# XMICRO-7SEG.net
KiCad netlist of a schematic drawn in EAGLE
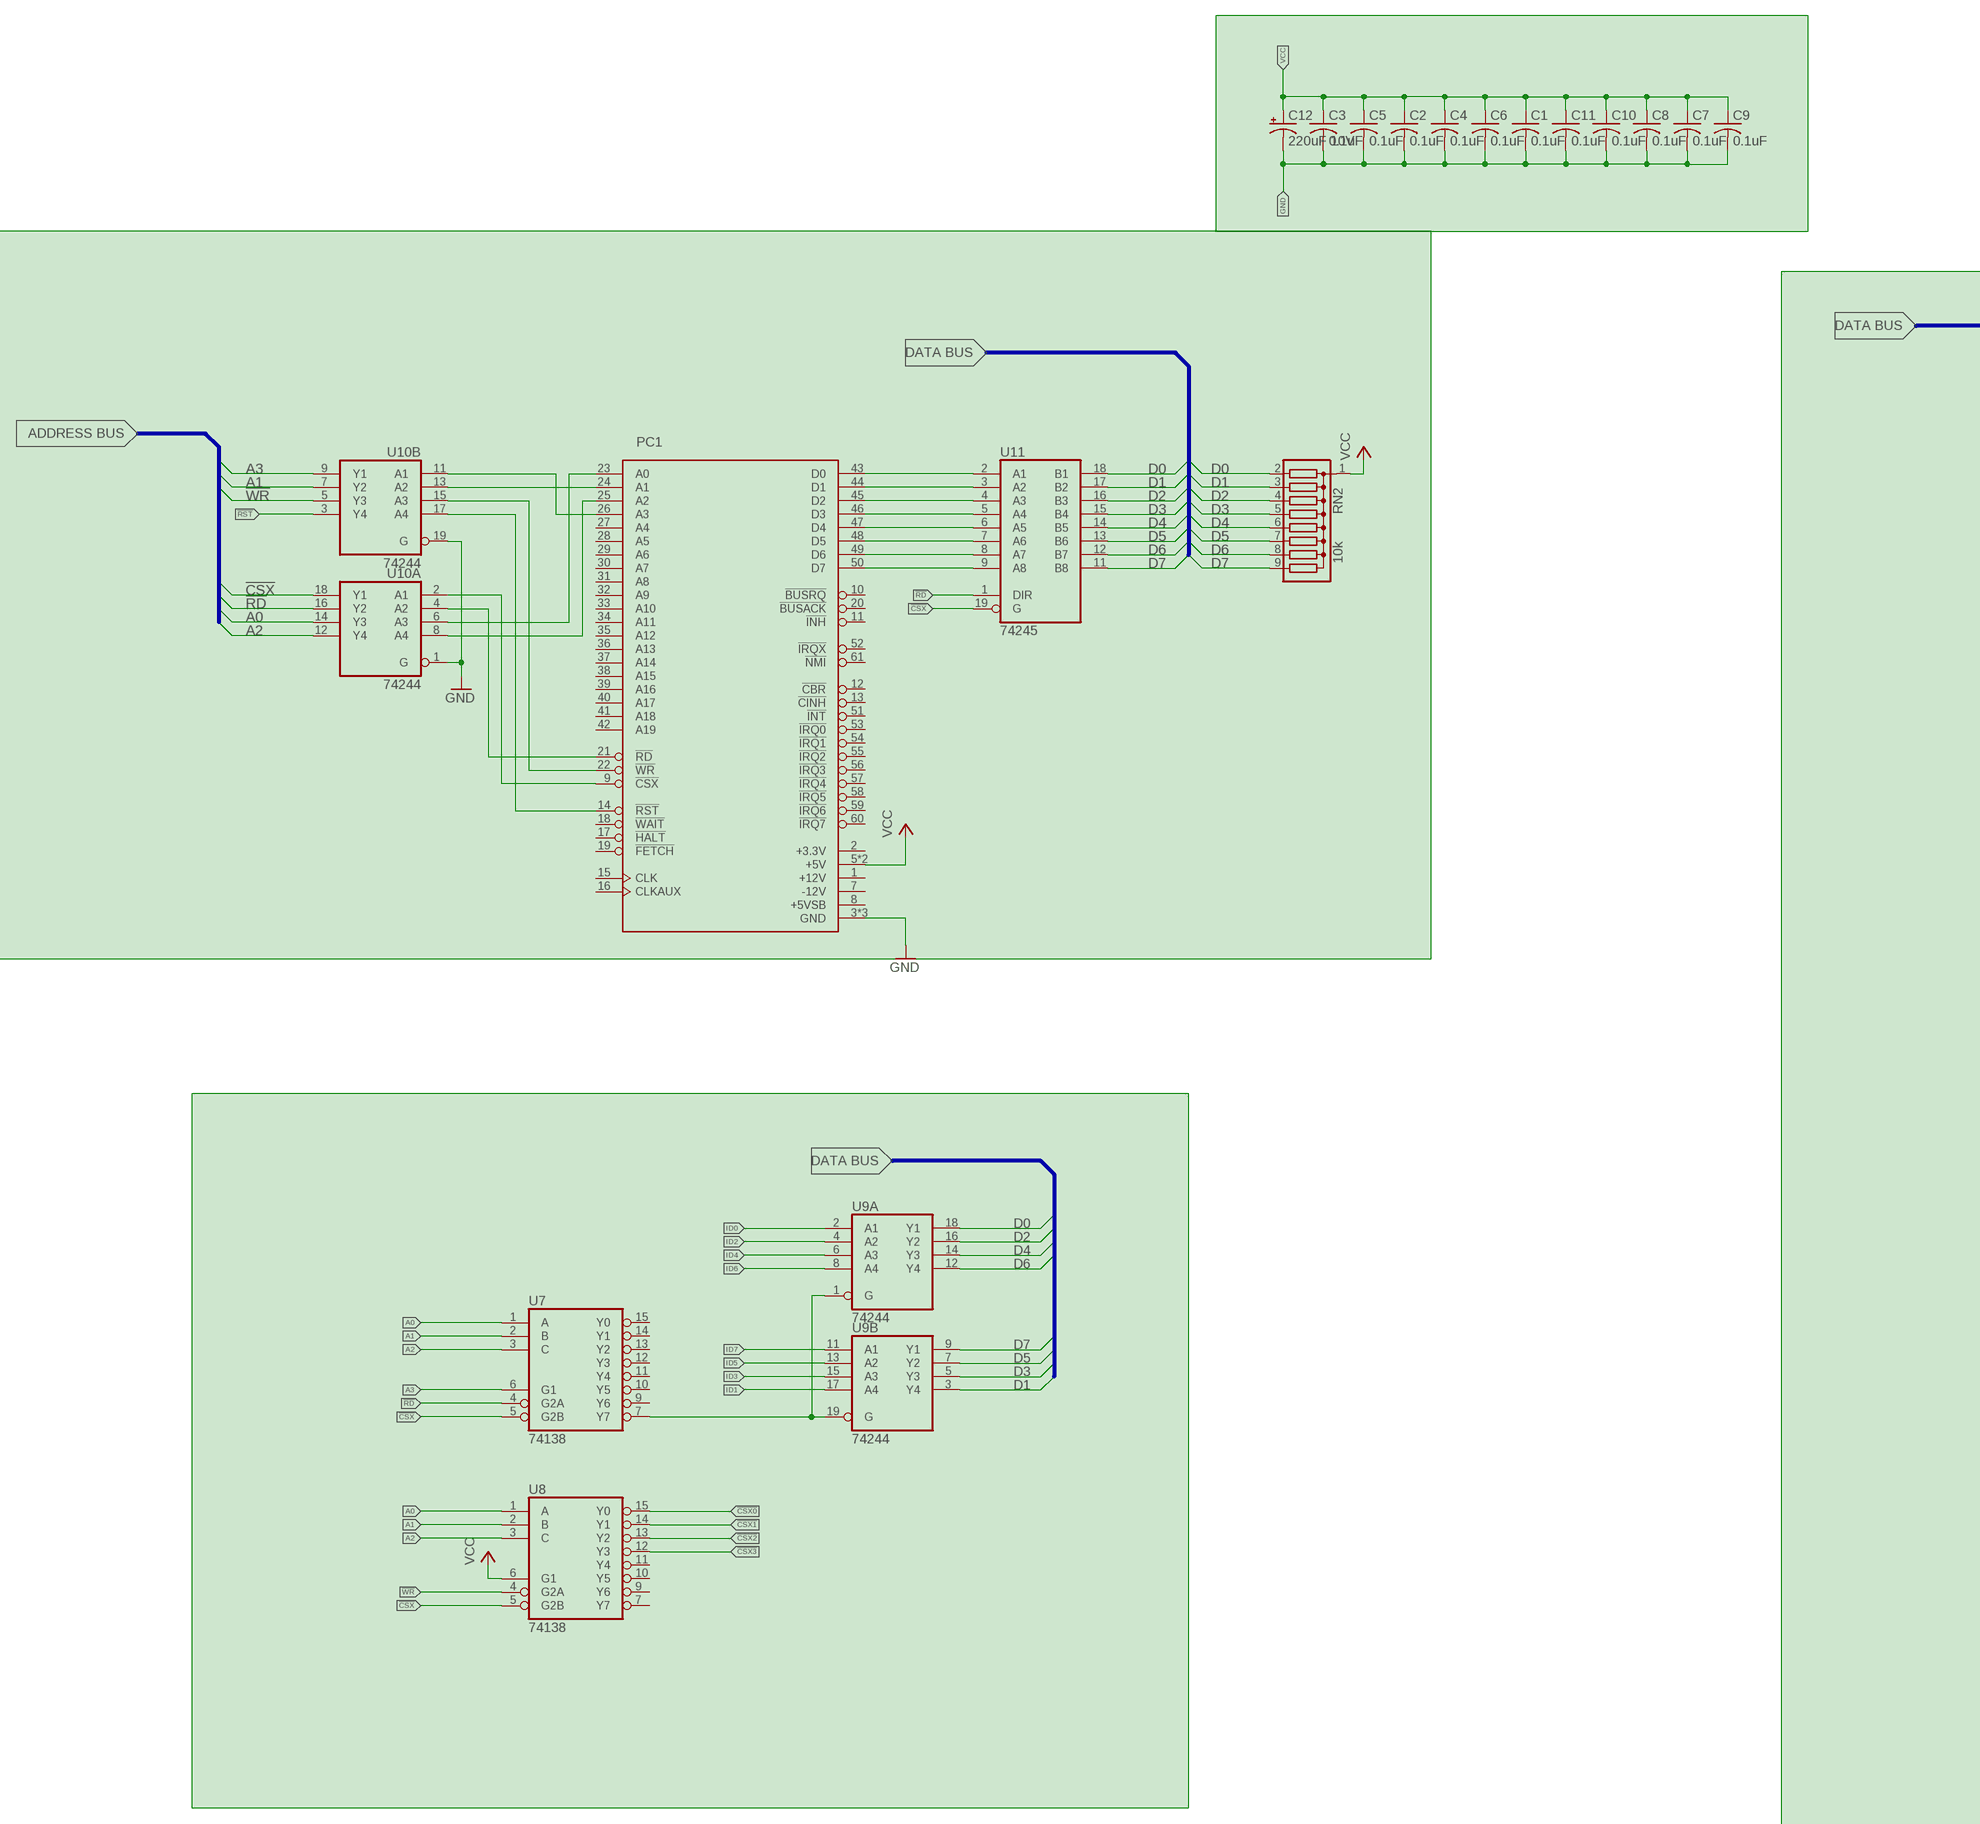
[diagram p0: schematic, sheet 1, part 1 of 2]
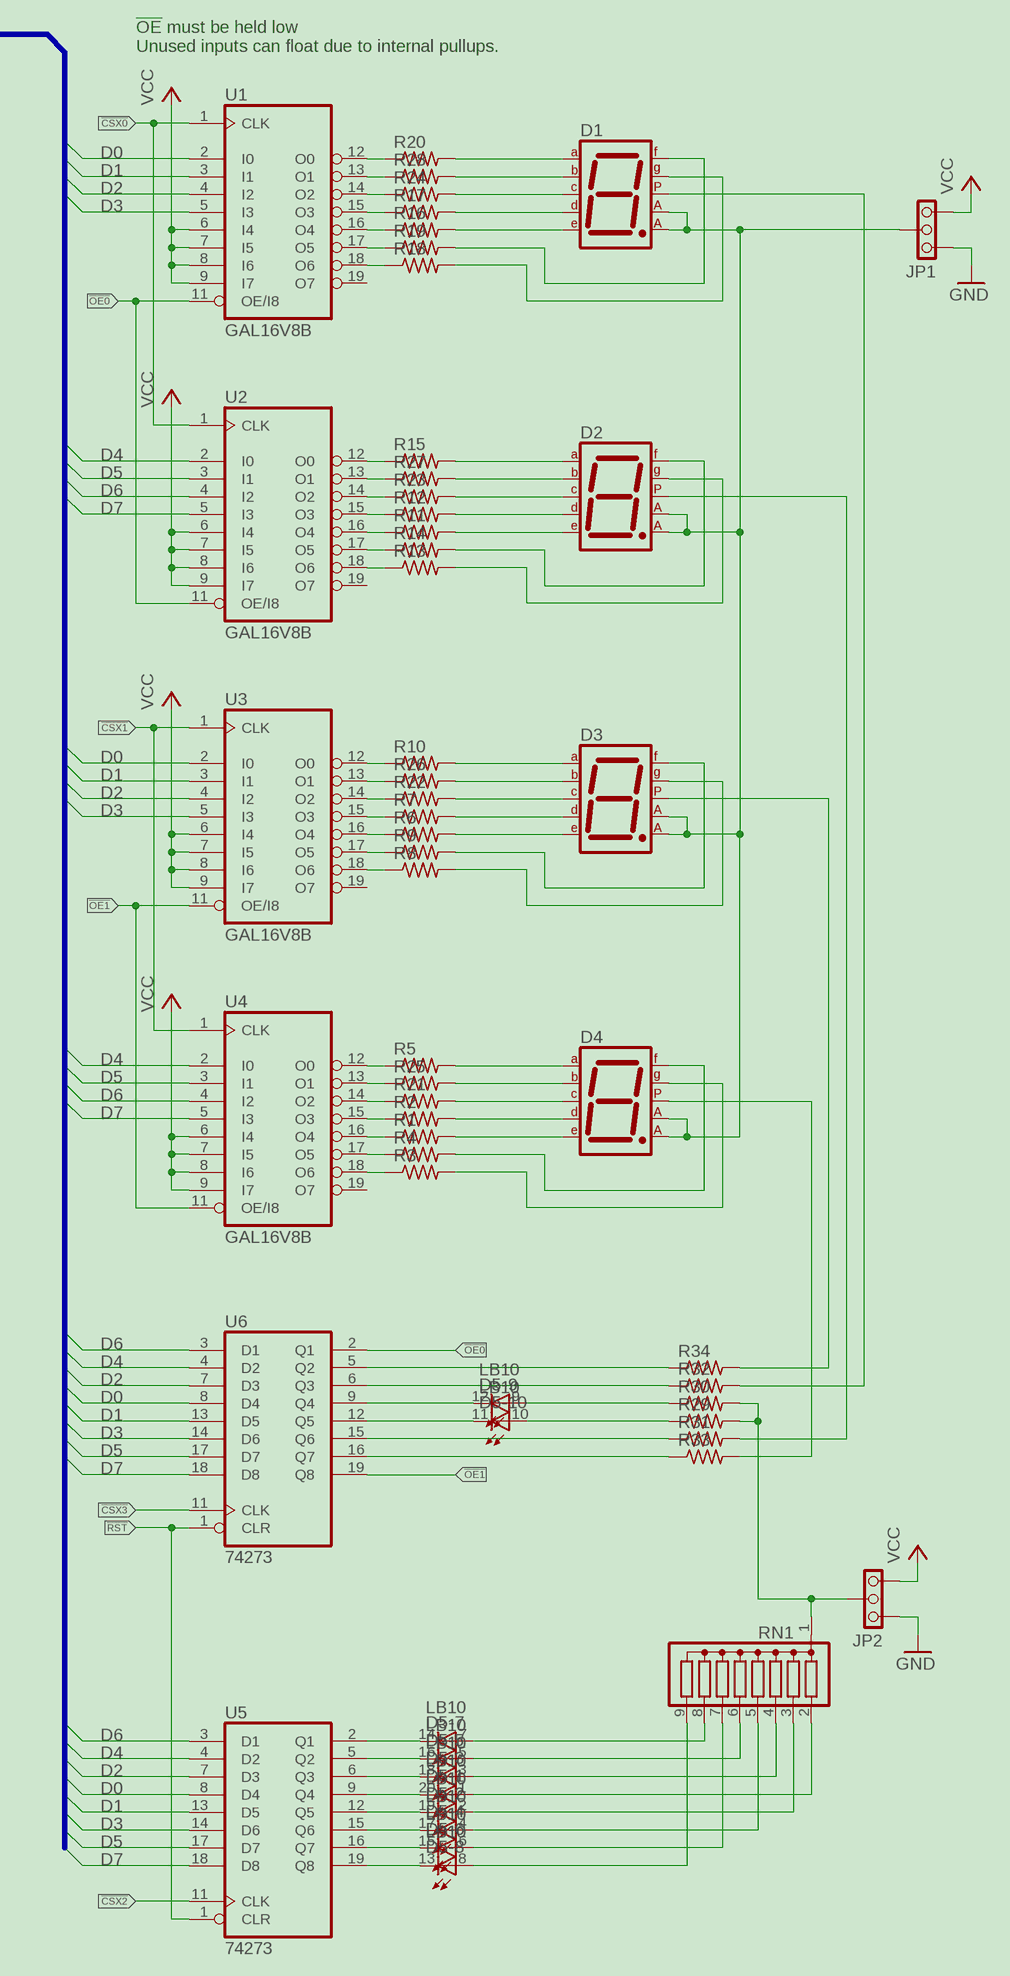
[diagram p1: schematic, sheet 1, part 2 of 2]

(export (version "E")
  (design (tool "Eeschema 10.0.6"))
  (components
    (comp (ref "C1")
      (value "0.1uF")
      (footprint "eagle-import:C025-024X044")
      (libsource (lib "eagle-import") (part "C-US025-024X044"))
    )
    (comp (ref "C2")
      (value "0.1uF")
      (footprint "eagle-import:C025-024X044")
      (libsource (lib "eagle-import") (part "C-US025-024X044"))
    )
    (comp (ref "C3")
      (value "0.1uF")
      (footprint "eagle-import:C025-024X044")
      (libsource (lib "eagle-import") (part "C-US025-024X044"))
    )
    (comp (ref "C4")
      (value "0.1uF")
      (footprint "eagle-import:C025-024X044")
      (libsource (lib "eagle-import") (part "C-US025-024X044"))
    )
    (comp (ref "C5")
      (value "0.1uF")
      (footprint "eagle-import:C025-024X044")
      (libsource (lib "eagle-import") (part "C-US025-024X044"))
    )
    (comp (ref "C6")
      (value "0.1uF")
      (footprint "eagle-import:C025-024X044")
      (libsource (lib "eagle-import") (part "C-US025-024X044"))
    )
    (comp (ref "C7")
      (value "0.1uF")
      (footprint "eagle-import:C025-024X044")
      (libsource (lib "eagle-import") (part "C-US025-024X044"))
    )
    (comp (ref "C8")
      (value "0.1uF")
      (footprint "eagle-import:C025-024X044")
      (libsource (lib "eagle-import") (part "C-US025-024X044"))
    )
    (comp (ref "C9")
      (value "0.1uF")
      (footprint "eagle-import:C025-024X044")
      (libsource (lib "eagle-import") (part "C-US025-024X044"))
    )
    (comp (ref "C10")
      (value "0.1uF")
      (footprint "eagle-import:C025-024X044")
      (libsource (lib "eagle-import") (part "C-US025-024X044"))
    )
    (comp (ref "C11")
      (value "0.1uF")
      (footprint "eagle-import:C025-024X044")
      (libsource (lib "eagle-import") (part "C-US025-024X044"))
    )
    (comp (ref "C12")
      (value "220uF 10V")
      (footprint "eagle-import:C-10-5")
      (libsource (lib "eagle-import") (part "CPOL-US-10-5"))
    )
    (comp (ref "D1")
      (value "7SEG-CA")
      (footprint "eagle-import:7SEG-13")
      (libsource (lib "eagle-import") (part "7SEG-CA"))
    )
    (comp (ref "D2")
      (value "7SEG-CA")
      (footprint "eagle-import:7SEG-13")
      (libsource (lib "eagle-import") (part "7SEG-CA"))
    )
    (comp (ref "D3")
      (value "7SEG-CA")
      (footprint "eagle-import:7SEG-13")
      (libsource (lib "eagle-import") (part "7SEG-CA"))
    )
    (comp (ref "D4")
      (value "7SEG-CA")
      (footprint "eagle-import:7SEG-13")
      (libsource (lib "eagle-import") (part "7SEG-CA"))
    )
    (comp (ref "D5")
      (value "LB10")
      (footprint "eagle-import:LB10")
      (libsource (lib "eagle-import") (part "LB10"))
    )
    (comp (ref "JP1")
      (value "PINHD1X3THRU")
      (footprint "eagle-import:1X03")
      (libsource (lib "eagle-import") (part "PINHD1X3THRU"))
    )
    (comp (ref "JP2")
      (value "PINHD1X3THRU")
      (footprint "eagle-import:1X03")
      (libsource (lib "eagle-import") (part "PINHD1X3THRU"))
    )
    (comp (ref "PC1")
      (value "XMICRO-BUS-EDGE62M")
      (footprint "eagle-import:EDGE62M")
      (libsource (lib "eagle-import") (part "XMICRO-BUS-EDGE62M"))
    )
    (comp (ref "R1")
      (value "R-US_0207/10")
      (footprint "eagle-import:0207_10")
      (libsource (lib "eagle-import") (part "R-US_0207/10"))
    )
    (comp (ref "R2")
      (value "R-US_0207/10")
      (footprint "eagle-import:0207_10")
      (libsource (lib "eagle-import") (part "R-US_0207/10"))
    )
    (comp (ref "R3")
      (value "R-US_0207/10")
      (footprint "eagle-import:0207_10")
      (libsource (lib "eagle-import") (part "R-US_0207/10"))
    )
    (comp (ref "R4")
      (value "R-US_0207/10")
      (footprint "eagle-import:0207_10")
      (libsource (lib "eagle-import") (part "R-US_0207/10"))
    )
    (comp (ref "R5")
      (value "R-US_0207/10")
      (footprint "eagle-import:0207_10")
      (libsource (lib "eagle-import") (part "R-US_0207/10"))
    )
    (comp (ref "R6")
      (value "R-US_0207/10")
      (footprint "eagle-import:0207_10")
      (libsource (lib "eagle-import") (part "R-US_0207/10"))
    )
    (comp (ref "R7")
      (value "R-US_0207/10")
      (footprint "eagle-import:0207_10")
      (libsource (lib "eagle-import") (part "R-US_0207/10"))
    )
    (comp (ref "R8")
      (value "R-US_0207/10")
      (footprint "eagle-import:0207_10")
      (libsource (lib "eagle-import") (part "R-US_0207/10"))
    )
    (comp (ref "R9")
      (value "R-US_0207/10")
      (footprint "eagle-import:0207_10")
      (libsource (lib "eagle-import") (part "R-US_0207/10"))
    )
    (comp (ref "R10")
      (value "R-US_0207/10")
      (footprint "eagle-import:0207_10")
      (libsource (lib "eagle-import") (part "R-US_0207/10"))
    )
    (comp (ref "R11")
      (value "R-US_0207/10")
      (footprint "eagle-import:0207_10")
      (libsource (lib "eagle-import") (part "R-US_0207/10"))
    )
    (comp (ref "R12")
      (value "R-US_0207/10")
      (footprint "eagle-import:0207_10")
      (libsource (lib "eagle-import") (part "R-US_0207/10"))
    )
    (comp (ref "R13")
      (value "R-US_0207/10")
      (footprint "eagle-import:0207_10")
      (libsource (lib "eagle-import") (part "R-US_0207/10"))
    )
    (comp (ref "R14")
      (value "R-US_0207/10")
      (footprint "eagle-import:0207_10")
      (libsource (lib "eagle-import") (part "R-US_0207/10"))
    )
    (comp (ref "R15")
      (value "R-US_0207/10")
      (footprint "eagle-import:0207_10")
      (libsource (lib "eagle-import") (part "R-US_0207/10"))
    )
    (comp (ref "R16")
      (value "R-US_0207/10")
      (footprint "eagle-import:0207_10")
      (libsource (lib "eagle-import") (part "R-US_0207/10"))
    )
    (comp (ref "R17")
      (value "R-US_0207/10")
      (footprint "eagle-import:0207_10")
      (libsource (lib "eagle-import") (part "R-US_0207/10"))
    )
    (comp (ref "R18")
      (value "R-US_0207/10")
      (footprint "eagle-import:0207_10")
      (libsource (lib "eagle-import") (part "R-US_0207/10"))
    )
    (comp (ref "R19")
      (value "R-US_0207/10")
      (footprint "eagle-import:0207_10")
      (libsource (lib "eagle-import") (part "R-US_0207/10"))
    )
    (comp (ref "R20")
      (value "R-US_0207/10")
      (footprint "eagle-import:0207_10")
      (libsource (lib "eagle-import") (part "R-US_0207/10"))
    )
    (comp (ref "R21")
      (value "R-US_0207/10")
      (footprint "eagle-import:0207_10")
      (libsource (lib "eagle-import") (part "R-US_0207/10"))
    )
    (comp (ref "R22")
      (value "R-US_0207/10")
      (footprint "eagle-import:0207_10")
      (libsource (lib "eagle-import") (part "R-US_0207/10"))
    )
    (comp (ref "R23")
      (value "R-US_0207/10")
      (footprint "eagle-import:0207_10")
      (libsource (lib "eagle-import") (part "R-US_0207/10"))
    )
    (comp (ref "R24")
      (value "R-US_0207/10")
      (footprint "eagle-import:0207_10")
      (libsource (lib "eagle-import") (part "R-US_0207/10"))
    )
    (comp (ref "R25")
      (value "R-US_0207/10")
      (footprint "eagle-import:0207_10")
      (libsource (lib "eagle-import") (part "R-US_0207/10"))
    )
    (comp (ref "R26")
      (value "R-US_0207/10")
      (footprint "eagle-import:0207_10")
      (libsource (lib "eagle-import") (part "R-US_0207/10"))
    )
    (comp (ref "R27")
      (value "R-US_0207/10")
      (footprint "eagle-import:0207_10")
      (libsource (lib "eagle-import") (part "R-US_0207/10"))
    )
    (comp (ref "R28")
      (value "R-US_0207/10")
      (footprint "eagle-import:0207_10")
      (libsource (lib "eagle-import") (part "R-US_0207/10"))
    )
    (comp (ref "R29")
      (value "R-US_0207/10")
      (footprint "eagle-import:0207_10")
      (libsource (lib "eagle-import") (part "R-US_0207/10"))
    )
    (comp (ref "R30")
      (value "R-US_0207/10")
      (footprint "eagle-import:0207_10")
      (libsource (lib "eagle-import") (part "R-US_0207/10"))
    )
    (comp (ref "R31")
      (value "R-US_0207/10")
      (footprint "eagle-import:0207_10")
      (libsource (lib "eagle-import") (part "R-US_0207/10"))
    )
    (comp (ref "R32")
      (value "R-US_0207/10")
      (footprint "eagle-import:0207_10")
      (libsource (lib "eagle-import") (part "R-US_0207/10"))
    )
    (comp (ref "R33")
      (value "R-US_0207/10")
      (footprint "eagle-import:0207_10")
      (libsource (lib "eagle-import") (part "R-US_0207/10"))
    )
    (comp (ref "R34")
      (value "R-US_0207/10")
      (footprint "eagle-import:0207_10")
      (libsource (lib "eagle-import") (part "R-US_0207/10"))
    )
    (comp (ref "RN1")
      (value "G08R")
      (footprint "eagle-import:SIL9")
      (libsource (lib "eagle-import") (part "G08R"))
    )
    (comp (ref "RN2")
      (value "10k")
      (footprint "eagle-import:SIL9")
      (fields (field (name "OC_FARNELL") "unknown") (field (name "OC_NEWARK") "unknown"))
      (libsource (lib "eagle-import") (part "G08R"))
    )
    (comp (ref "U1")
      (value "GAL16V8B")
      (footprint "eagle-import:DIL20")
      (fields (field (name "MPN") "GAL16V8D-7LPN"))
      (libsource (lib "eagle-import") (part "16V8"))
    )
    (comp (ref "U2")
      (value "GAL16V8B")
      (footprint "eagle-import:DIL20")
      (fields (field (name "MPN") "GAL16V8D-7LPN"))
      (libsource (lib "eagle-import") (part "16V8"))
    )
    (comp (ref "U3")
      (value "GAL16V8B")
      (footprint "eagle-import:DIL20")
      (fields (field (name "MPN") "GAL16V8D-7LPN"))
      (libsource (lib "eagle-import") (part "16V8"))
    )
    (comp (ref "U4")
      (value "GAL16V8B")
      (footprint "eagle-import:DIL20")
      (fields (field (name "MPN") "GAL16V8D-7LPN"))
      (libsource (lib "eagle-import") (part "16V8"))
    )
    (comp (ref "U5")
      (value "74273")
      (footprint "eagle-import:DIL20")
      (libsource (lib "eagle-import") (part "74273N"))
    )
    (comp (ref "U6")
      (value "74273")
      (footprint "eagle-import:DIL20")
      (libsource (lib "eagle-import") (part "74273N"))
    )
    (comp (ref "U7")
      (value "74138")
      (footprint "eagle-import:DIL16")
      (libsource (lib "eagle-import") (part "74138NLS"))
    )
    (comp (ref "U8")
      (value "74138")
      (footprint "eagle-import:DIL16")
      (libsource (lib "eagle-import") (part "74138NLS"))
    )
    (comp (ref "U9")
      (value "74244")
      (footprint "eagle-import:DIL20")
      (libsource (lib "eagle-import") (part "74244NLS"))
    )
    (comp (ref "U10")
      (value "74244")
      (footprint "eagle-import:DIL20")
      (libsource (lib "eagle-import") (part "74244NLS"))
    )
    (comp (ref "U11")
      (value "74245")
      (footprint "eagle-import:DIL20")
      (libsource (lib "eagle-import") (part "74245NLS"))
    )
  )
  (nets
    (net (code "1") (name "/D0") (class "Default")
      (node (ref "RN2") (pin "2") (pinfunction "2_2") (pintype "passive"))
      (node (ref "U1") (pin "2") (pinfunction "I0_2") (pintype "input"))
      (node (ref "U11") (pin "18") (pinfunction "B1_18") (pintype "bidirectional"))
      (node (ref "U3") (pin "2") (pinfunction "I0_2") (pintype "input"))
      (node (ref "U5") (pin "8") (pinfunction "D4_8") (pintype "input"))
      (node (ref "U6") (pin "8") (pinfunction "D4_8") (pintype "input"))
      (node (ref "U9") (pin "18") (pinfunction "Y1_18") (pintype "tri_state"))
    )
    (net (code "2") (name "/D1") (class "Default")
      (node (ref "RN2") (pin "3") (pinfunction "3_3") (pintype "passive"))
      (node (ref "U1") (pin "3") (pinfunction "I1_3") (pintype "input"))
      (node (ref "U11") (pin "17") (pinfunction "B2_17") (pintype "bidirectional"))
      (node (ref "U3") (pin "3") (pinfunction "I1_3") (pintype "input"))
      (node (ref "U5") (pin "13") (pinfunction "D5_13") (pintype "input"))
      (node (ref "U6") (pin "13") (pinfunction "D5_13") (pintype "input"))
      (node (ref "U9") (pin "3") (pinfunction "Y4_3") (pintype "tri_state"))
    )
    (net (code "3") (name "/D2") (class "Default")
      (node (ref "RN2") (pin "4") (pinfunction "4_4") (pintype "passive"))
      (node (ref "U1") (pin "4") (pinfunction "I2_4") (pintype "input"))
      (node (ref "U11") (pin "16") (pinfunction "B3_16") (pintype "bidirectional"))
      (node (ref "U3") (pin "4") (pinfunction "I2_4") (pintype "input"))
      (node (ref "U5") (pin "7") (pinfunction "D3_7") (pintype "input"))
      (node (ref "U6") (pin "7") (pinfunction "D3_7") (pintype "input"))
      (node (ref "U9") (pin "16") (pinfunction "Y2_16") (pintype "tri_state"))
    )
    (net (code "4") (name "/D3") (class "Default")
      (node (ref "RN2") (pin "5") (pinfunction "5_5") (pintype "passive"))
      (node (ref "U1") (pin "5") (pinfunction "I3_5") (pintype "input"))
      (node (ref "U11") (pin "15") (pinfunction "B4_15") (pintype "bidirectional"))
      (node (ref "U3") (pin "5") (pinfunction "I3_5") (pintype "input"))
      (node (ref "U5") (pin "14") (pinfunction "D6_14") (pintype "input"))
      (node (ref "U6") (pin "14") (pinfunction "D6_14") (pintype "input"))
      (node (ref "U9") (pin "5") (pinfunction "Y3_5") (pintype "tri_state"))
    )
    (net (code "5") (name "/D4") (class "Default")
      (node (ref "RN2") (pin "6") (pinfunction "6_6") (pintype "passive"))
      (node (ref "U11") (pin "14") (pinfunction "B5_14") (pintype "bidirectional"))
      (node (ref "U2") (pin "2") (pinfunction "I0_2") (pintype "input"))
      (node (ref "U4") (pin "2") (pinfunction "I0_2") (pintype "input"))
      (node (ref "U5") (pin "4") (pinfunction "D2_4") (pintype "input"))
      (node (ref "U6") (pin "4") (pinfunction "D2_4") (pintype "input"))
      (node (ref "U9") (pin "14") (pinfunction "Y3_14") (pintype "tri_state"))
    )
    (net (code "6") (name "/D5") (class "Default")
      (node (ref "RN2") (pin "7") (pinfunction "7_7") (pintype "passive"))
      (node (ref "U11") (pin "13") (pinfunction "B6_13") (pintype "bidirectional"))
      (node (ref "U2") (pin "3") (pinfunction "I1_3") (pintype "input"))
      (node (ref "U4") (pin "3") (pinfunction "I1_3") (pintype "input"))
      (node (ref "U5") (pin "17") (pinfunction "D7_17") (pintype "input"))
      (node (ref "U6") (pin "17") (pinfunction "D7_17") (pintype "input"))
      (node (ref "U9") (pin "7") (pinfunction "Y2_7") (pintype "tri_state"))
    )
    (net (code "7") (name "/D6") (class "Default")
      (node (ref "RN2") (pin "8") (pinfunction "8_8") (pintype "passive"))
      (node (ref "U11") (pin "12") (pinfunction "B7_12") (pintype "bidirectional"))
      (node (ref "U2") (pin "4") (pinfunction "I2_4") (pintype "input"))
      (node (ref "U4") (pin "4") (pinfunction "I2_4") (pintype "input"))
      (node (ref "U5") (pin "3") (pinfunction "D1_3") (pintype "input"))
      (node (ref "U6") (pin "3") (pinfunction "D1_3") (pintype "input"))
      (node (ref "U9") (pin "12") (pinfunction "Y4_12") (pintype "tri_state"))
    )
    (net (code "8") (name "/D7") (class "Default")
      (node (ref "RN2") (pin "9") (pinfunction "9_9") (pintype "passive"))
      (node (ref "U11") (pin "11") (pinfunction "B8_11") (pintype "bidirectional"))
      (node (ref "U2") (pin "5") (pinfunction "I3_5") (pintype "input"))
      (node (ref "U4") (pin "5") (pinfunction "I3_5") (pintype "input"))
      (node (ref "U5") (pin "18") (pinfunction "D8_18") (pintype "input"))
      (node (ref "U6") (pin "18") (pinfunction "D8_18") (pintype "input"))
      (node (ref "U9") (pin "9") (pinfunction "Y1_9") (pintype "tri_state"))
    )
    (net (code "10") (name "/~{CSX0}") (class "Default")
      (node (ref "U1") (pin "1") (pinfunction "CLK_1") (pintype "input"))
      (node (ref "U2") (pin "1") (pinfunction "CLK_1") (pintype "input"))
      (node (ref "U8") (pin "15") (pinfunction "Y0_15") (pintype "output"))
    )
    (net (code "11") (name "/~{CSX1}") (class "Default")
      (node (ref "U3") (pin "1") (pinfunction "CLK_1") (pintype "input"))
      (node (ref "U4") (pin "1") (pinfunction "CLK_1") (pintype "input"))
      (node (ref "U8") (pin "14") (pinfunction "Y1_14") (pintype "output"))
    )
    (net (code "12") (name "/~{CSX2}") (class "Default")
      (node (ref "U5") (pin "11") (pinfunction "CLK_11") (pintype "input"))
      (node (ref "U8") (pin "13") (pinfunction "Y2_13") (pintype "output"))
    )
    (net (code "13") (name "/~{CSX3}") (class "Default")
      (node (ref "U6") (pin "11") (pinfunction "CLK_11") (pintype "input"))
      (node (ref "U8") (pin "12") (pinfunction "Y3_12") (pintype "output"))
    )
    (net (code "14") (name "/~{CSX}") (class "Default")
      (node (ref "U10") (pin "18") (pinfunction "Y1_18") (pintype "tri_state"))
      (node (ref "U11") (pin "19") (pinfunction "G_19") (pintype "input"))
      (node (ref "U7") (pin "5") (pinfunction "G2B_5") (pintype "input"))
      (node (ref "U8") (pin "5") (pinfunction "G2B_5") (pintype "input"))
    )
    (net (code "15") (name "/~{OE0}") (class "Default")
      (node (ref "U1") (pin "11") (pinfunction "OE/I8_11") (pintype "input"))
      (node (ref "U2") (pin "11") (pinfunction "OE/I8_11") (pintype "input"))
      (node (ref "U6") (pin "2") (pinfunction "Q1_2") (pintype "output"))
    )
    (net (code "16") (name "/~{OE1}") (class "Default")
      (node (ref "U3") (pin "11") (pinfunction "OE/I8_11") (pintype "input"))
      (node (ref "U4") (pin "11") (pinfunction "OE/I8_11") (pintype "input"))
      (node (ref "U6") (pin "19") (pinfunction "Q8_19") (pintype "output"))
    )
    (net (code "17") (name "/~{RD}") (class "Default")
      (node (ref "U10") (pin "16") (pinfunction "Y2_16") (pintype "tri_state"))
      (node (ref "U11") (pin "1") (pinfunction "DIR_1") (pintype "input"))
      (node (ref "U7") (pin "4") (pinfunction "G2A_4") (pintype "input"))
    )
    (net (code "18") (name "/~{RST}") (class "Default")
      (node (ref "U10") (pin "3") (pinfunction "Y4_3") (pintype "tri_state"))
      (node (ref "U5") (pin "1") (pinfunction "CLR_1") (pintype "input"))
      (node (ref "U6") (pin "1") (pinfunction "CLR_1") (pintype "input"))
    )
    (net (code "19") (name "/~{WR}") (class "Default")
      (node (ref "U10") (pin "5") (pinfunction "Y3_5") (pintype "tri_state"))
      (node (ref "U8") (pin "4") (pinfunction "G2A_4") (pintype "input"))
    )
    (net (code "20") (name "A0") (class "Default")
      (node (ref "U10") (pin "14") (pinfunction "Y3_14") (pintype "tri_state"))
      (node (ref "U7") (pin "1") (pinfunction "A_1") (pintype "input"))
      (node (ref "U8") (pin "1") (pinfunction "A_1") (pintype "input"))
    )
    (net (code "21") (name "A1") (class "Default")
      (node (ref "U10") (pin "7") (pinfunction "Y2_7") (pintype "tri_state"))
      (node (ref "U7") (pin "2") (pinfunction "B_2") (pintype "input"))
      (node (ref "U8") (pin "2") (pinfunction "B_2") (pintype "input"))
    )
    (net (code "22") (name "A2") (class "Default")
      (node (ref "U10") (pin "12") (pinfunction "Y4_12") (pintype "tri_state"))
      (node (ref "U7") (pin "3") (pinfunction "C_3") (pintype "input"))
      (node (ref "U8") (pin "3") (pinfunction "C_3") (pintype "input"))
    )
    (net (code "23") (name "A3") (class "Default")
      (node (ref "U10") (pin "9") (pinfunction "Y1_9") (pintype "tri_state"))
      (node (ref "U7") (pin "6") (pinfunction "G1_6") (pintype "input"))
    )
    (net (code "24") (name "GND") (class "Default")
      (node (ref "C1") (pin "2") (pinfunction "2_2") (pintype "passive"))
      (node (ref "C10") (pin "2") (pinfunction "2_2") (pintype "passive"))
      (node (ref "C11") (pin "2") (pinfunction "2_2") (pintype "passive"))
      (node (ref "C12") (pin "-") (pinfunction "-_-") (pintype "passive"))
      (node (ref "C2") (pin "2") (pinfunction "2_2") (pintype "passive"))
      (node (ref "C3") (pin "2") (pinfunction "2_2") (pintype "passive"))
      (node (ref "C4") (pin "2") (pinfunction "2_2") (pintype "passive"))
      (node (ref "C5") (pin "2") (pinfunction "2_2") (pintype "passive"))
      (node (ref "C6") (pin "2") (pinfunction "2_2") (pintype "passive"))
      (node (ref "C7") (pin "2") (pinfunction "2_2") (pintype "passive"))
      (node (ref "C8") (pin "2") (pinfunction "2_2") (pintype "passive"))
      (node (ref "C9") (pin "2") (pinfunction "2_2") (pintype "passive"))
      (node (ref "JP1") (pin "1") (pinfunction "1_1") (pintype "passive"))
      (node (ref "JP2") (pin "1") (pinfunction "1_1") (pintype "passive"))
      (node (ref "PC1") (pin "3") (pinfunction "GND_3") (pintype "bidirectional"))
      (node (ref "PC1") (pin "4") (pinfunction "GND_4") (pintype "bidirectional"))
      (node (ref "PC1") (pin "62") (pinfunction "GND_62") (pintype "bidirectional"))
      (node (ref "U10") (pin "1") (pinfunction "G_1") (pintype "input"))
      (node (ref "U10") (pin "19") (pinfunction "G_19") (pintype "input"))
    )
    (net (code "25") (name "ID0") (class "Default")
      (node (ref "U9") (pin "2") (pinfunction "A1_2") (pintype "input"))
    )
    (net (code "26") (name "ID1") (class "Default")
      (node (ref "U9") (pin "17") (pinfunction "A4_17") (pintype "input"))
    )
    (net (code "27") (name "ID2") (class "Default")
      (node (ref "U9") (pin "4") (pinfunction "A2_4") (pintype "input"))
    )
    (net (code "28") (name "ID3") (class "Default")
      (node (ref "U9") (pin "15") (pinfunction "A3_15") (pintype "input"))
    )
    (net (code "29") (name "ID4") (class "Default")
      (node (ref "U9") (pin "6") (pinfunction "A3_6") (pintype "input"))
    )
    (net (code "30") (name "ID5") (class "Default")
      (node (ref "U9") (pin "13") (pinfunction "A2_13") (pintype "input"))
    )
    (net (code "31") (name "ID6") (class "Default")
      (node (ref "U9") (pin "8") (pinfunction "A4_8") (pintype "input"))
    )
    (net (code "32") (name "ID7") (class "Default")
      (node (ref "U9") (pin "11") (pinfunction "A1_11") (pintype "input"))
    )
    (net (code "33") (name "Net-(D1-A)") (class "Default")
      (node (ref "D1") (pin "7") (pinfunction "A_7") (pintype "passive"))
      (node (ref "R20") (pin "2") (pinfunction "2_2") (pintype "passive"))
    )
    (net (code "34") (name "Net-(D1-B)") (class "Default")
      (node (ref "D1") (pin "6") (pinfunction "B_6") (pintype "passive"))
      (node (ref "R28") (pin "2") (pinfunction "2_2") (pintype "passive"))
    )
    (net (code "35") (name "Net-(D1-C)") (class "Default")
      (node (ref "D1") (pin "4") (pinfunction "C_4") (pintype "passive"))
      (node (ref "R24") (pin "2") (pinfunction "2_2") (pintype "passive"))
    )
    (net (code "36") (name "Net-(D1-CA1)") (class "Default")
      (node (ref "D1") (pin "3") (pinfunction "CA1_3") (pintype "passive"))
      (node (ref "D1") (pin "8") (pinfunction "CA2_8") (pintype "passive"))
      (node (ref "D2") (pin "3") (pinfunction "CA1_3") (pintype "passive"))
      (node (ref "D2") (pin "8") (pinfunction "CA2_8") (pintype "passive"))
      (node (ref "D3") (pin "3") (pinfunction "CA1_3") (pintype "passive"))
      (node (ref "D3") (pin "8") (pinfunction "CA2_8") (pintype "passive"))
      (node (ref "D4") (pin "3") (pinfunction "CA1_3") (pintype "passive"))
      (node (ref "D4") (pin "8") (pinfunction "CA2_8") (pintype "passive"))
      (node (ref "JP1") (pin "2") (pinfunction "2_2") (pintype "passive"))
    )
    (net (code "37") (name "Net-(D1-D)") (class "Default")
      (node (ref "D1") (pin "2") (pinfunction "D_2") (pintype "passive"))
      (node (ref "R17") (pin "2") (pinfunction "2_2") (pintype "passive"))
    )
    (net (code "38") (name "Net-(D1-DP)") (class "Default")
      (node (ref "D1") (pin "5") (pinfunction "DP_5") (pintype "passive"))
      (node (ref "R32") (pin "2") (pinfunction "2_2") (pintype "passive"))
    )
    (net (code "39") (name "Net-(D1-E)") (class "Default")
      (node (ref "D1") (pin "1") (pinfunction "E_1") (pintype "passive"))
      (node (ref "R16") (pin "2") (pinfunction "2_2") (pintype "passive"))
    )
    (net (code "40") (name "Net-(D1-F)") (class "Default")
      (node (ref "D1") (pin "9") (pinfunction "F_9") (pintype "passive"))
      (node (ref "R19") (pin "2") (pinfunction "2_2") (pintype "passive"))
    )
    (net (code "41") (name "Net-(D1-G)") (class "Default")
      (node (ref "D1") (pin "10") (pinfunction "G_10") (pintype "passive"))
      (node (ref "R18") (pin "2") (pinfunction "2_2") (pintype "passive"))
    )
    (net (code "42") (name "Net-(D2-A)") (class "Default")
      (node (ref "D2") (pin "7") (pinfunction "A_7") (pintype "passive"))
      (node (ref "R15") (pin "2") (pinfunction "2_2") (pintype "passive"))
    )
    (net (code "43") (name "Net-(D2-B)") (class "Default")
      (node (ref "D2") (pin "6") (pinfunction "B_6") (pintype "passive"))
      (node (ref "R27") (pin "2") (pinfunction "2_2") (pintype "passive"))
    )
    (net (code "44") (name "Net-(D2-C)") (class "Default")
      (node (ref "D2") (pin "4") (pinfunction "C_4") (pintype "passive"))
      (node (ref "R23") (pin "2") (pinfunction "2_2") (pintype "passive"))
    )
    (net (code "45") (name "Net-(D2-D)") (class "Default")
      (node (ref "D2") (pin "2") (pinfunction "D_2") (pintype "passive"))
      (node (ref "R12") (pin "2") (pinfunction "2_2") (pintype "passive"))
    )
    (net (code "46") (name "Net-(D2-DP)") (class "Default")
      (node (ref "D2") (pin "5") (pinfunction "DP_5") (pintype "passive"))
      (node (ref "R31") (pin "2") (pinfunction "2_2") (pintype "passive"))
    )
    (net (code "47") (name "Net-(D2-E)") (class "Default")
      (node (ref "D2") (pin "1") (pinfunction "E_1") (pintype "passive"))
      (node (ref "R11") (pin "2") (pinfunction "2_2") (pintype "passive"))
    )
    (net (code "48") (name "Net-(D2-F)") (class "Default")
      (node (ref "D2") (pin "9") (pinfunction "F_9") (pintype "passive"))
      (node (ref "R14") (pin "2") (pinfunction "2_2") (pintype "passive"))
    )
    (net (code "49") (name "Net-(D2-G)") (class "Default")
      (node (ref "D2") (pin "10") (pinfunction "G_10") (pintype "passive"))
      (node (ref "R13") (pin "2") (pinfunction "2_2") (pintype "passive"))
    )
    (net (code "50") (name "Net-(D3-A)") (class "Default")
      (node (ref "D3") (pin "7") (pinfunction "A_7") (pintype "passive"))
      (node (ref "R10") (pin "2") (pinfunction "2_2") (pintype "passive"))
    )
    (net (code "51") (name "Net-(D3-B)") (class "Default")
      (node (ref "D3") (pin "6") (pinfunction "B_6") (pintype "passive"))
      (node (ref "R26") (pin "2") (pinfunction "2_2") (pintype "passive"))
    )
    (net (code "52") (name "Net-(D3-C)") (class "Default")
      (node (ref "D3") (pin "4") (pinfunction "C_4") (pintype "passive"))
      (node (ref "R22") (pin "2") (pinfunction "2_2") (pintype "passive"))
    )
    (net (code "53") (name "Net-(D3-D)") (class "Default")
      (node (ref "D3") (pin "2") (pinfunction "D_2") (pintype "passive"))
      (node (ref "R7") (pin "2") (pinfunction "2_2") (pintype "passive"))
    )
    (net (code "54") (name "Net-(D3-DP)") (class "Default")
      (node (ref "D3") (pin "5") (pinfunction "DP_5") (pintype "passive"))
      (node (ref "R34") (pin "2") (pinfunction "2_2") (pintype "passive"))
    )
    (net (code "55") (name "Net-(D3-E)") (class "Default")
      (node (ref "D3") (pin "1") (pinfunction "E_1") (pintype "passive"))
      (node (ref "R6") (pin "2") (pinfunction "2_2") (pintype "passive"))
    )
    (net (code "56") (name "Net-(D3-F)") (class "Default")
      (node (ref "D3") (pin "9") (pinfunction "F_9") (pintype "passive"))
      (node (ref "R9") (pin "2") (pinfunction "2_2") (pintype "passive"))
    )
    (net (code "57") (name "Net-(D3-G)") (class "Default")
      (node (ref "D3") (pin "10") (pinfunction "G_10") (pintype "passive"))
      (node (ref "R8") (pin "2") (pinfunction "2_2") (pintype "passive"))
    )
    (net (code "58") (name "Net-(D4-A)") (class "Default")
      (node (ref "D4") (pin "7") (pinfunction "A_7") (pintype "passive"))
      (node (ref "R5") (pin "2") (pinfunction "2_2") (pintype "passive"))
    )
    (net (code "59") (name "Net-(D4-B)") (class "Default")
      (node (ref "D4") (pin "6") (pinfunction "B_6") (pintype "passive"))
      (node (ref "R25") (pin "2") (pinfunction "2_2") (pintype "passive"))
    )
    (net (code "60") (name "Net-(D4-C)") (class "Default")
      (node (ref "D4") (pin "4") (pinfunction "C_4") (pintype "passive"))
      (node (ref "R21") (pin "2") (pinfunction "2_2") (pintype "passive"))
    )
    (net (code "61") (name "Net-(D4-D)") (class "Default")
      (node (ref "D4") (pin "2") (pinfunction "D_2") (pintype "passive"))
      (node (ref "R2") (pin "2") (pinfunction "2_2") (pintype "passive"))
    )
    (net (code "62") (name "Net-(D4-DP)") (class "Default")
      (node (ref "D4") (pin "5") (pinfunction "DP_5") (pintype "passive"))
      (node (ref "R33") (pin "2") (pinfunction "2_2") (pintype "passive"))
    )
    (net (code "63") (name "Net-(D4-E)") (class "Default")
      (node (ref "D4") (pin "1") (pinfunction "E_1") (pintype "passive"))
      (node (ref "R1") (pin "2") (pinfunction "2_2") (pintype "passive"))
    )
    (net (code "64") (name "Net-(D4-F)") (class "Default")
      (node (ref "D4") (pin "9") (pinfunction "F_9") (pintype "passive"))
      (node (ref "R4") (pin "2") (pinfunction "2_2") (pintype "passive"))
    )
    (net (code "65") (name "Net-(D4-G)") (class "Default")
      (node (ref "D4") (pin "10") (pinfunction "G_10") (pintype "passive"))
      (node (ref "R3") (pin "2") (pinfunction "2_2") (pintype "passive"))
    )
    (net (code "66") (name "Net-(D5A-A)") (class "Default")
      (node (ref "D5") (pin "1") (pinfunction "A_1") (pintype "passive"))
      (node (ref "RN1") (pin "2") (pinfunction "2_2") (pintype "passive"))
    )
    (net (code "67") (name "Net-(D5A-C)") (class "Default")
      (node (ref "D5") (pin "20") (pinfunction "C_20") (pintype "passive"))
      (node (ref "U5") (pin "9") (pinfunction "Q4_9") (pintype "output"))
    )
    (net (code "68") (name "Net-(D5B-A)") (class "Default")
      (node (ref "D5") (pin "10") (pinfunction "A_10") (pintype "passive"))
      (node (ref "R29") (pin "1") (pinfunction "1_1") (pintype "passive"))
    )
    (net (code "69") (name "Net-(D5B-C)") (class "Default")
      (node (ref "D5") (pin "11") (pinfunction "C_11") (pintype "passive"))
      (node (ref "U6") (pin "12") (pinfunction "Q5_12") (pintype "output"))
    )
    (net (code "70") (name "Net-(D5C-A)") (class "Default")
      (node (ref "D5") (pin "2") (pinfunction "A_2") (pintype "passive"))
      (node (ref "RN1") (pin "3") (pinfunction "3_3") (pintype "passive"))
    )
    (net (code "71") (name "Net-(D5C-C)") (class "Default")
      (node (ref "D5") (pin "19") (pinfunction "C_19") (pintype "passive"))
      (node (ref "U5") (pin "12") (pinfunction "Q5_12") (pintype "output"))
    )
    (net (code "72") (name "Net-(D5D-A)") (class "Default")
      (node (ref "D5") (pin "3") (pinfunction "A_3") (pintype "passive"))
      (node (ref "RN1") (pin "4") (pinfunction "4_4") (pintype "passive"))
    )
    (net (code "73") (name "Net-(D5D-C)") (class "Default")
      (node (ref "D5") (pin "18") (pinfunction "C_18") (pintype "passive"))
      (node (ref "U5") (pin "6") (pinfunction "Q3_6") (pintype "output"))
    )
    (net (code "74") (name "Net-(D5E-A)") (class "Default")
      (node (ref "D5") (pin "4") (pinfunction "A_4") (pintype "passive"))
      (node (ref "RN1") (pin "5") (pinfunction "5_5") (pintype "passive"))
    )
    (net (code "75") (name "Net-(D5E-C)") (class "Default")
      (node (ref "D5") (pin "17") (pinfunction "C_17") (pintype "passive"))
      (node (ref "U5") (pin "15") (pinfunction "Q6_15") (pintype "output"))
    )
    (net (code "76") (name "Net-(D5F-A)") (class "Default")
      (node (ref "D5") (pin "5") (pinfunction "A_5") (pintype "passive"))
      (node (ref "RN1") (pin "6") (pinfunction "6_6") (pintype "passive"))
    )
    (net (code "77") (name "Net-(D5F-C)") (class "Default")
      (node (ref "D5") (pin "16") (pinfunction "C_16") (pintype "passive"))
      (node (ref "U5") (pin "5") (pinfunction "Q2_5") (pintype "output"))
    )
    (net (code "78") (name "Net-(D5G-A)") (class "Default")
      (node (ref "D5") (pin "6") (pinfunction "A_6") (pintype "passive"))
      (node (ref "RN1") (pin "7") (pinfunction "7_7") (pintype "passive"))
    )
    (net (code "79") (name "Net-(D5G-C)") (class "Default")
      (node (ref "D5") (pin "15") (pinfunction "C_15") (pintype "passive"))
      (node (ref "U5") (pin "16") (pinfunction "Q7_16") (pintype "output"))
    )
    (net (code "80") (name "Net-(D5H-A)") (class "Default")
      (node (ref "D5") (pin "7") (pinfunction "A_7") (pintype "passive"))
      (node (ref "RN1") (pin "8") (pinfunction "8_8") (pintype "passive"))
    )
    (net (code "81") (name "Net-(D5H-C)") (class "Default")
      (node (ref "D5") (pin "14") (pinfunction "C_14") (pintype "passive"))
      (node (ref "U5") (pin "2") (pinfunction "Q1_2") (pintype "output"))
    )
    (net (code "82") (name "Net-(D5I-A)") (class "Default")
      (node (ref "D5") (pin "8") (pinfunction "A_8") (pintype "passive"))
      (node (ref "RN1") (pin "9") (pinfunction "9_9") (pintype "passive"))
    )
    (net (code "83") (name "Net-(D5I-C)") (class "Default")
      (node (ref "D5") (pin "13") (pinfunction "C_13") (pintype "passive"))
      (node (ref "U5") (pin "19") (pinfunction "Q8_19") (pintype "output"))
    )
    (net (code "84") (name "Net-(D5J-A)") (class "Default")
      (node (ref "D5") (pin "9") (pinfunction "A_9") (pintype "passive"))
      (node (ref "R30") (pin "1") (pinfunction "1_1") (pintype "passive"))
    )
    (net (code "85") (name "Net-(D5J-C)") (class "Default")
      (node (ref "D5") (pin "12") (pinfunction "C_12") (pintype "passive"))
      (node (ref "U6") (pin "9") (pinfunction "Q4_9") (pintype "output"))
    )
    (net (code "86") (name "Net-(JP2-Pad2)") (class "Default")
      (node (ref "JP2") (pin "2") (pinfunction "2_2") (pintype "passive"))
      (node (ref "R29") (pin "2") (pinfunction "2_2") (pintype "passive"))
      (node (ref "R30") (pin "2") (pinfunction "2_2") (pintype "passive"))
      (node (ref "RN1") (pin "1") (pinfunction "1_1") (pintype "passive"))
    )
    (net (code "87") (name "Net-(PC1-A0)") (class "Default")
      (node (ref "PC1") (pin "23") (pinfunction "A0_23") (pintype "bidirectional"))
      (node (ref "U10") (pin "6") (pinfunction "A3_6") (pintype "input"))
    )
    (net (code "88") (name "Net-(PC1-A1)") (class "Default")
      (node (ref "PC1") (pin "24") (pinfunction "A1_24") (pintype "bidirectional"))
      (node (ref "U10") (pin "13") (pinfunction "A2_13") (pintype "input"))
    )
    (net (code "89") (name "Net-(PC1-A2)") (class "Default")
      (node (ref "PC1") (pin "25") (pinfunction "A2_25") (pintype "bidirectional"))
      (node (ref "U10") (pin "8") (pinfunction "A4_8") (pintype "input"))
    )
    (net (code "90") (name "Net-(PC1-A3)") (class "Default")
      (node (ref "PC1") (pin "26") (pinfunction "A3_26") (pintype "bidirectional"))
      (node (ref "U10") (pin "11") (pinfunction "A1_11") (pintype "input"))
    )
    (net (code "91") (name "Net-(PC1-D0)") (class "Default")
      (node (ref "PC1") (pin "43") (pinfunction "D0_43") (pintype "bidirectional"))
      (node (ref "U11") (pin "2") (pinfunction "A1_2") (pintype "bidirectional"))
    )
    (net (code "92") (name "Net-(PC1-D1)") (class "Default")
      (node (ref "PC1") (pin "44") (pinfunction "D1_44") (pintype "bidirectional"))
      (node (ref "U11") (pin "3") (pinfunction "A2_3") (pintype "bidirectional"))
    )
    (net (code "93") (name "Net-(PC1-D2)") (class "Default")
      (node (ref "PC1") (pin "45") (pinfunction "D2_45") (pintype "bidirectional"))
      (node (ref "U11") (pin "4") (pinfunction "A3_4") (pintype "bidirectional"))
    )
    (net (code "94") (name "Net-(PC1-D3)") (class "Default")
      (node (ref "PC1") (pin "46") (pinfunction "D3_46") (pintype "bidirectional"))
      (node (ref "U11") (pin "5") (pinfunction "A4_5") (pintype "bidirectional"))
    )
    (net (code "95") (name "Net-(PC1-D4)") (class "Default")
      (node (ref "PC1") (pin "47") (pinfunction "D4_47") (pintype "bidirectional"))
      (node (ref "U11") (pin "6") (pinfunction "A5_6") (pintype "bidirectional"))
    )
    (net (code "96") (name "Net-(PC1-D5)") (class "Default")
      (node (ref "PC1") (pin "48") (pinfunction "D5_48") (pintype "bidirectional"))
      (node (ref "U11") (pin "7") (pinfunction "A6_7") (pintype "bidirectional"))
    )
    (net (code "97") (name "Net-(PC1-D6)") (class "Default")
      (node (ref "PC1") (pin "49") (pinfunction "D6_49") (pintype "bidirectional"))
      (node (ref "U11") (pin "8") (pinfunction "A7_8") (pintype "bidirectional"))
    )
    (net (code "98") (name "Net-(PC1-D7)") (class "Default")
      (node (ref "PC1") (pin "50") (pinfunction "D7_50") (pintype "bidirectional"))
      (node (ref "U11") (pin "9") (pinfunction "A8_9") (pintype "bidirectional"))
    )
    (net (code "99") (name "Net-(PC1-~{CSX})") (class "Default")
      (node (ref "PC1") (pin "9") (pinfunction "~{CSX}_9") (pintype "bidirectional"))
      (node (ref "U10") (pin "2") (pinfunction "A1_2") (pintype "input"))
    )
    (net (code "100") (name "Net-(PC1-~{RD})") (class "Default")
      (node (ref "PC1") (pin "21") (pinfunction "~{RD}_21") (pintype "bidirectional"))
      (node (ref "U10") (pin "4") (pinfunction "A2_4") (pintype "input"))
    )
    (net (code "101") (name "Net-(PC1-~{RST})") (class "Default")
      (node (ref "PC1") (pin "14") (pinfunction "~{RST}_14") (pintype "bidirectional"))
      (node (ref "U10") (pin "17") (pinfunction "A4_17") (pintype "input"))
    )
    (net (code "102") (name "Net-(PC1-~{WR})") (class "Default")
      (node (ref "PC1") (pin "22") (pinfunction "~{WR}_22") (pintype "bidirectional"))
      (node (ref "U10") (pin "15") (pinfunction "A3_15") (pintype "input"))
    )
    (net (code "103") (name "Net-(U1A-O0)") (class "Default")
      (node (ref "R20") (pin "1") (pinfunction "1_1") (pintype "passive"))
      (node (ref "U1") (pin "12") (pinfunction "O0_12") (pintype "bidirectional"))
    )
    (net (code "104") (name "Net-(U1A-O1)") (class "Default")
      (node (ref "R28") (pin "1") (pinfunction "1_1") (pintype "passive"))
      (node (ref "U1") (pin "13") (pinfunction "O1_13") (pintype "bidirectional"))
    )
    (net (code "105") (name "Net-(U1A-O2)") (class "Default")
      (node (ref "R24") (pin "1") (pinfunction "1_1") (pintype "passive"))
      (node (ref "U1") (pin "14") (pinfunction "O2_14") (pintype "bidirectional"))
    )
    (net (code "106") (name "Net-(U1A-O3)") (class "Default")
      (node (ref "R17") (pin "1") (pinfunction "1_1") (pintype "passive"))
      (node (ref "U1") (pin "15") (pinfunction "O3_15") (pintype "bidirectional"))
    )
    (net (code "107") (name "Net-(U1A-O4)") (class "Default")
      (node (ref "R16") (pin "1") (pinfunction "1_1") (pintype "passive"))
      (node (ref "U1") (pin "16") (pinfunction "O4_16") (pintype "bidirectional"))
    )
    (net (code "108") (name "Net-(U1A-O5)") (class "Default")
      (node (ref "R19") (pin "1") (pinfunction "1_1") (pintype "passive"))
      (node (ref "U1") (pin "17") (pinfunction "O5_17") (pintype "bidirectional"))
    )
    (net (code "109") (name "Net-(U1A-O6)") (class "Default")
      (node (ref "R18") (pin "1") (pinfunction "1_1") (pintype "passive"))
      (node (ref "U1") (pin "18") (pinfunction "O6_18") (pintype "bidirectional"))
    )
    (net (code "110") (name "Net-(U2A-O0)") (class "Default")
      (node (ref "R15") (pin "1") (pinfunction "1_1") (pintype "passive"))
      (node (ref "U2") (pin "12") (pinfunction "O0_12") (pintype "bidirectional"))
    )
    (net (code "111") (name "Net-(U2A-O1)") (class "Default")
      (node (ref "R27") (pin "1") (pinfunction "1_1") (pintype "passive"))
      (node (ref "U2") (pin "13") (pinfunction "O1_13") (pintype "bidirectional"))
    )
    (net (code "112") (name "Net-(U2A-O2)") (class "Default")
      (node (ref "R23") (pin "1") (pinfunction "1_1") (pintype "passive"))
      (node (ref "U2") (pin "14") (pinfunction "O2_14") (pintype "bidirectional"))
    )
    (net (code "113") (name "Net-(U2A-O3)") (class "Default")
      (node (ref "R12") (pin "1") (pinfunction "1_1") (pintype "passive"))
      (node (ref "U2") (pin "15") (pinfunction "O3_15") (pintype "bidirectional"))
    )
    (net (code "114") (name "Net-(U2A-O4)") (class "Default")
      (node (ref "R11") (pin "1") (pinfunction "1_1") (pintype "passive"))
      (node (ref "U2") (pin "16") (pinfunction "O4_16") (pintype "bidirectional"))
    )
    (net (code "115") (name "Net-(U2A-O5)") (class "Default")
      (node (ref "R14") (pin "1") (pinfunction "1_1") (pintype "passive"))
      (node (ref "U2") (pin "17") (pinfunction "O5_17") (pintype "bidirectional"))
    )
    (net (code "116") (name "Net-(U2A-O6)") (class "Default")
      (node (ref "R13") (pin "1") (pinfunction "1_1") (pintype "passive"))
      (node (ref "U2") (pin "18") (pinfunction "O6_18") (pintype "bidirectional"))
    )
    (net (code "117") (name "Net-(U3A-O0)") (class "Default")
      (node (ref "R10") (pin "1") (pinfunction "1_1") (pintype "passive"))
      (node (ref "U3") (pin "12") (pinfunction "O0_12") (pintype "bidirectional"))
    )
    (net (code "118") (name "Net-(U3A-O1)") (class "Default")
      (node (ref "R26") (pin "1") (pinfunction "1_1") (pintype "passive"))
      (node (ref "U3") (pin "13") (pinfunction "O1_13") (pintype "bidirectional"))
    )
    (net (code "119") (name "Net-(U3A-O2)") (class "Default")
      (node (ref "R22") (pin "1") (pinfunction "1_1") (pintype "passive"))
      (node (ref "U3") (pin "14") (pinfunction "O2_14") (pintype "bidirectional"))
    )
    (net (code "120") (name "Net-(U3A-O3)") (class "Default")
      (node (ref "R7") (pin "1") (pinfunction "1_1") (pintype "passive"))
      (node (ref "U3") (pin "15") (pinfunction "O3_15") (pintype "bidirectional"))
    )
    (net (code "121") (name "Net-(U3A-O4)") (class "Default")
      (node (ref "R6") (pin "1") (pinfunction "1_1") (pintype "passive"))
      (node (ref "U3") (pin "16") (pinfunction "O4_16") (pintype "bidirectional"))
    )
    (net (code "122") (name "Net-(U3A-O5)") (class "Default")
      (node (ref "R9") (pin "1") (pinfunction "1_1") (pintype "passive"))
      (node (ref "U3") (pin "17") (pinfunction "O5_17") (pintype "bidirectional"))
    )
    (net (code "123") (name "Net-(U3A-O6)") (class "Default")
      (node (ref "R8") (pin "1") (pinfunction "1_1") (pintype "passive"))
      (node (ref "U3") (pin "18") (pinfunction "O6_18") (pintype "bidirectional"))
    )
    (net (code "124") (name "Net-(U4A-O0)") (class "Default")
      (node (ref "R5") (pin "1") (pinfunction "1_1") (pintype "passive"))
      (node (ref "U4") (pin "12") (pinfunction "O0_12") (pintype "bidirectional"))
    )
    (net (code "125") (name "Net-(U4A-O1)") (class "Default")
      (node (ref "R25") (pin "1") (pinfunction "1_1") (pintype "passive"))
      (node (ref "U4") (pin "13") (pinfunction "O1_13") (pintype "bidirectional"))
    )
    (net (code "126") (name "Net-(U4A-O2)") (class "Default")
      (node (ref "R21") (pin "1") (pinfunction "1_1") (pintype "passive"))
      (node (ref "U4") (pin "14") (pinfunction "O2_14") (pintype "bidirectional"))
    )
    (net (code "127") (name "Net-(U4A-O3)") (class "Default")
      (node (ref "R2") (pin "1") (pinfunction "1_1") (pintype "passive"))
      (node (ref "U4") (pin "15") (pinfunction "O3_15") (pintype "bidirectional"))
    )
    (net (code "128") (name "Net-(U4A-O4)") (class "Default")
      (node (ref "R1") (pin "1") (pinfunction "1_1") (pintype "passive"))
      (node (ref "U4") (pin "16") (pinfunction "O4_16") (pintype "bidirectional"))
    )
    (net (code "129") (name "Net-(U4A-O5)") (class "Default")
      (node (ref "R4") (pin "1") (pinfunction "1_1") (pintype "passive"))
      (node (ref "U4") (pin "17") (pinfunction "O5_17") (pintype "bidirectional"))
    )
    (net (code "130") (name "Net-(U4A-O6)") (class "Default")
      (node (ref "R3") (pin "1") (pinfunction "1_1") (pintype "passive"))
      (node (ref "U4") (pin "18") (pinfunction "O6_18") (pintype "bidirectional"))
    )
    (net (code "131") (name "Net-(U6A-Q2)") (class "Default")
      (node (ref "R34") (pin "1") (pinfunction "1_1") (pintype "passive"))
      (node (ref "U6") (pin "5") (pinfunction "Q2_5") (pintype "output"))
    )
    (net (code "132") (name "Net-(U6A-Q3)") (class "Default")
      (node (ref "R32") (pin "1") (pinfunction "1_1") (pintype "passive"))
      (node (ref "U6") (pin "6") (pinfunction "Q3_6") (pintype "output"))
    )
    (net (code "133") (name "Net-(U6A-Q6)") (class "Default")
      (node (ref "R31") (pin "1") (pinfunction "1_1") (pintype "passive"))
      (node (ref "U6") (pin "15") (pinfunction "Q6_15") (pintype "output"))
    )
    (net (code "134") (name "Net-(U6A-Q7)") (class "Default")
      (node (ref "R33") (pin "1") (pinfunction "1_1") (pintype "passive"))
      (node (ref "U6") (pin "16") (pinfunction "Q7_16") (pintype "output"))
    )
    (net (code "135") (name "Net-(U7A-Y7)") (class "Default")
      (node (ref "U7") (pin "7") (pinfunction "Y7_7") (pintype "output"))
      (node (ref "U9") (pin "1") (pinfunction "G_1") (pintype "input"))
      (node (ref "U9") (pin "19") (pinfunction "G_19") (pintype "input"))
    )
    (net (code "136") (name "VCC") (class "Default")
      (node (ref "C1") (pin "1") (pinfunction "1_1") (pintype "passive"))
      (node (ref "C10") (pin "1") (pinfunction "1_1") (pintype "passive"))
      (node (ref "C11") (pin "1") (pinfunction "1_1") (pintype "passive"))
      (node (ref "C12") (pin "+") (pinfunction "+_+") (pintype "passive"))
      (node (ref "C2") (pin "1") (pinfunction "1_1") (pintype "passive"))
      (node (ref "C3") (pin "1") (pinfunction "1_1") (pintype "passive"))
      (node (ref "C4") (pin "1") (pinfunction "1_1") (pintype "passive"))
      (node (ref "C5") (pin "1") (pinfunction "1_1") (pintype "passive"))
      (node (ref "C6") (pin "1") (pinfunction "1_1") (pintype "passive"))
      (node (ref "C7") (pin "1") (pinfunction "1_1") (pintype "passive"))
      (node (ref "C8") (pin "1") (pinfunction "1_1") (pintype "passive"))
      (node (ref "C9") (pin "1") (pinfunction "1_1") (pintype "passive"))
      (node (ref "JP1") (pin "3") (pinfunction "3_3") (pintype "passive"))
      (node (ref "JP2") (pin "3") (pinfunction "3_3") (pintype "passive"))
      (node (ref "PC1") (pin "5") (pinfunction "+5V_5") (pintype "bidirectional"))
      (node (ref "PC1") (pin "6") (pinfunction "+5V_6") (pintype "bidirectional"))
      (node (ref "RN2") (pin "1") (pinfunction "1_1") (pintype "passive"))
      (node (ref "U1") (pin "6") (pinfunction "I4_6") (pintype "input"))
      (node (ref "U1") (pin "7") (pinfunction "I5_7") (pintype "input"))
      (node (ref "U1") (pin "8") (pinfunction "I6_8") (pintype "input"))
      (node (ref "U1") (pin "9") (pinfunction "I7_9") (pintype "input"))
      (node (ref "U2") (pin "6") (pinfunction "I4_6") (pintype "input"))
      (node (ref "U2") (pin "7") (pinfunction "I5_7") (pintype "input"))
      (node (ref "U2") (pin "8") (pinfunction "I6_8") (pintype "input"))
      (node (ref "U2") (pin "9") (pinfunction "I7_9") (pintype "input"))
      (node (ref "U3") (pin "6") (pinfunction "I4_6") (pintype "input"))
      (node (ref "U3") (pin "7") (pinfunction "I5_7") (pintype "input"))
      (node (ref "U3") (pin "8") (pinfunction "I6_8") (pintype "input"))
      (node (ref "U3") (pin "9") (pinfunction "I7_9") (pintype "input"))
      (node (ref "U4") (pin "6") (pinfunction "I4_6") (pintype "input"))
      (node (ref "U4") (pin "7") (pinfunction "I5_7") (pintype "input"))
      (node (ref "U4") (pin "8") (pinfunction "I6_8") (pintype "input"))
      (node (ref "U4") (pin "9") (pinfunction "I7_9") (pintype "input"))
      (node (ref "U8") (pin "6") (pinfunction "G1_6") (pintype "input"))
    )
    (net (code "137") (name "unconnected-(PC1-+3.3V-Pad2)") (class "Default")
      (node (ref "PC1") (pin "2") (pinfunction "+3.3V_2") (pintype "bidirectional"))
    )
    (net (code "138") (name "unconnected-(PC1-+5VSB-Pad8)") (class "Default")
      (node (ref "PC1") (pin "8") (pinfunction "+5VSB_8") (pintype "bidirectional"))
    )
    (net (code "139") (name "unconnected-(PC1-+12V-Pad1)") (class "Default")
      (node (ref "PC1") (pin "1") (pinfunction "+12V_1") (pintype "bidirectional"))
    )
    (net (code "140") (name "unconnected-(PC1--12V-Pad7)") (class "Default")
      (node (ref "PC1") (pin "7") (pinfunction "-12V_7") (pintype "bidirectional"))
    )
    (net (code "141") (name "unconnected-(PC1-A4-Pad27)") (class "Default")
      (node (ref "PC1") (pin "27") (pinfunction "A4_27") (pintype "bidirectional"))
    )
    (net (code "142") (name "unconnected-(PC1-A5-Pad28)") (class "Default")
      (node (ref "PC1") (pin "28") (pinfunction "A5_28") (pintype "bidirectional"))
    )
    (net (code "143") (name "unconnected-(PC1-A6-Pad29)") (class "Default")
      (node (ref "PC1") (pin "29") (pinfunction "A6_29") (pintype "bidirectional"))
    )
    (net (code "144") (name "unconnected-(PC1-A7-Pad30)") (class "Default")
      (node (ref "PC1") (pin "30") (pinfunction "A7_30") (pintype "bidirectional"))
    )
    (net (code "145") (name "unconnected-(PC1-A8-Pad31)") (class "Default")
      (node (ref "PC1") (pin "31") (pinfunction "A8_31") (pintype "bidirectional"))
    )
    (net (code "146") (name "unconnected-(PC1-A9-Pad32)") (class "Default")
      (node (ref "PC1") (pin "32") (pinfunction "A9_32") (pintype "bidirectional"))
    )
    (net (code "147") (name "unconnected-(PC1-A10-Pad33)") (class "Default")
      (node (ref "PC1") (pin "33") (pinfunction "A10_33") (pintype "bidirectional"))
    )
    (net (code "148") (name "unconnected-(PC1-A11-Pad34)") (class "Default")
      (node (ref "PC1") (pin "34") (pinfunction "A11_34") (pintype "bidirectional"))
    )
    (net (code "149") (name "unconnected-(PC1-A12-Pad35)") (class "Default")
      (node (ref "PC1") (pin "35") (pinfunction "A12_35") (pintype "bidirectional"))
    )
    (net (code "150") (name "unconnected-(PC1-A13-Pad36)") (class "Default")
      (node (ref "PC1") (pin "36") (pinfunction "A13_36") (pintype "bidirectional"))
    )
    (net (code "151") (name "unconnected-(PC1-A14-Pad37)") (class "Default")
      (node (ref "PC1") (pin "37") (pinfunction "A14_37") (pintype "bidirectional"))
    )
    (net (code "152") (name "unconnected-(PC1-A15-Pad38)") (class "Default")
      (node (ref "PC1") (pin "38") (pinfunction "A15_38") (pintype "bidirectional"))
    )
    (net (code "153") (name "unconnected-(PC1-A16-Pad39)") (class "Default")
      (node (ref "PC1") (pin "39") (pinfunction "A16_39") (pintype "bidirectional"))
    )
    (net (code "154") (name "unconnected-(PC1-A17-Pad40)") (class "Default")
      (node (ref "PC1") (pin "40") (pinfunction "A17_40") (pintype "bidirectional"))
    )
    (net (code "155") (name "unconnected-(PC1-A18-Pad41)") (class "Default")
      (node (ref "PC1") (pin "41") (pinfunction "A18_41") (pintype "bidirectional"))
    )
    (net (code "156") (name "unconnected-(PC1-A19-Pad42)") (class "Default")
      (node (ref "PC1") (pin "42") (pinfunction "A19_42") (pintype "bidirectional"))
    )
    (net (code "157") (name "unconnected-(PC1-CLK-Pad15)") (class "Default")
      (node (ref "PC1") (pin "15") (pinfunction "CLK_15") (pintype "bidirectional"))
    )
    (net (code "158") (name "unconnected-(PC1-CLKAUX-Pad16)") (class "Default")
      (node (ref "PC1") (pin "16") (pinfunction "CLKAUX_16") (pintype "bidirectional"))
    )
    (net (code "159") (name "unconnected-(PC1-~{BUSACK}-Pad20)") (class "Default")
      (node (ref "PC1") (pin "20") (pinfunction "~{BUSACK}_20") (pintype "bidirectional"))
    )
    (net (code "160") (name "unconnected-(PC1-~{BUSRQ}-Pad10)") (class "Default")
      (node (ref "PC1") (pin "10") (pinfunction "~{BUSRQ}_10") (pintype "bidirectional"))
    )
    (net (code "161") (name "unconnected-(PC1-~{CBR}-Pad12)") (class "Default")
      (node (ref "PC1") (pin "12") (pinfunction "~{CBR}_12") (pintype "bidirectional"))
    )
    (net (code "162") (name "unconnected-(PC1-~{CINH}-Pad13)") (class "Default")
      (node (ref "PC1") (pin "13") (pinfunction "~{CINH}_13") (pintype "bidirectional"))
    )
    (net (code "163") (name "unconnected-(PC1-~{FETCH}-Pad19)") (class "Default")
      (node (ref "PC1") (pin "19") (pinfunction "~{FETCH}_19") (pintype "bidirectional"))
    )
    (net (code "164") (name "unconnected-(PC1-~{HALT}-Pad17)") (class "Default")
      (node (ref "PC1") (pin "17") (pinfunction "~{HALT}_17") (pintype "bidirectional"))
    )
    (net (code "165") (name "unconnected-(PC1-~{INH}-Pad11)") (class "Default")
      (node (ref "PC1") (pin "11") (pinfunction "~{INH}_11") (pintype "bidirectional"))
    )
    (net (code "166") (name "unconnected-(PC1-~{INT}-Pad51)") (class "Default")
      (node (ref "PC1") (pin "51") (pinfunction "~{INT}_51") (pintype "bidirectional"))
    )
    (net (code "167") (name "unconnected-(PC1-~{IRQ0}-Pad53)") (class "Default")
      (node (ref "PC1") (pin "53") (pinfunction "~{IRQ0}_53") (pintype "bidirectional"))
    )
    (net (code "168") (name "unconnected-(PC1-~{IRQ1}-Pad54)") (class "Default")
      (node (ref "PC1") (pin "54") (pinfunction "~{IRQ1}_54") (pintype "bidirectional"))
    )
    (net (code "169") (name "unconnected-(PC1-~{IRQ2}-Pad55)") (class "Default")
      (node (ref "PC1") (pin "55") (pinfunction "~{IRQ2}_55") (pintype "bidirectional"))
    )
    (net (code "170") (name "unconnected-(PC1-~{IRQ3}-Pad56)") (class "Default")
      (node (ref "PC1") (pin "56") (pinfunction "~{IRQ3}_56") (pintype "bidirectional"))
    )
    (net (code "171") (name "unconnected-(PC1-~{IRQ4}-Pad57)") (class "Default")
      (node (ref "PC1") (pin "57") (pinfunction "~{IRQ4}_57") (pintype "bidirectional"))
    )
    (net (code "172") (name "unconnected-(PC1-~{IRQ5}-Pad58)") (class "Default")
      (node (ref "PC1") (pin "58") (pinfunction "~{IRQ5}_58") (pintype "bidirectional"))
    )
    (net (code "173") (name "unconnected-(PC1-~{IRQ6}-Pad59)") (class "Default")
      (node (ref "PC1") (pin "59") (pinfunction "~{IRQ6}_59") (pintype "bidirectional"))
    )
    (net (code "174") (name "unconnected-(PC1-~{IRQ7}-Pad60)") (class "Default")
      (node (ref "PC1") (pin "60") (pinfunction "~{IRQ7}_60") (pintype "bidirectional"))
    )
    (net (code "175") (name "unconnected-(PC1-~{IRQX}-Pad52)") (class "Default")
      (node (ref "PC1") (pin "52") (pinfunction "~{IRQX}_52") (pintype "bidirectional"))
    )
    (net (code "176") (name "unconnected-(PC1-~{NMI}-Pad61)") (class "Default")
      (node (ref "PC1") (pin "61") (pinfunction "~{NMI}_61") (pintype "bidirectional"))
    )
    (net (code "177") (name "unconnected-(PC1-~{WAIT}-Pad18)") (class "Default")
      (node (ref "PC1") (pin "18") (pinfunction "~{WAIT}_18") (pintype "bidirectional"))
    )
    (net (code "178") (name "unconnected-(U1A-O7-Pad19)") (class "Default")
      (node (ref "U1") (pin "19") (pinfunction "O7_19") (pintype "bidirectional"))
    )
    (net (code "179") (name "unconnected-(U2A-O7-Pad19)") (class "Default")
      (node (ref "U2") (pin "19") (pinfunction "O7_19") (pintype "bidirectional"))
    )
    (net (code "180") (name "unconnected-(U3A-O7-Pad19)") (class "Default")
      (node (ref "U3") (pin "19") (pinfunction "O7_19") (pintype "bidirectional"))
    )
    (net (code "181") (name "unconnected-(U4A-O7-Pad19)") (class "Default")
      (node (ref "U4") (pin "19") (pinfunction "O7_19") (pintype "bidirectional"))
    )
    (net (code "182") (name "unconnected-(U7A-Y0-Pad15)") (class "Default")
      (node (ref "U7") (pin "15") (pinfunction "Y0_15") (pintype "output"))
    )
    (net (code "183") (name "unconnected-(U7A-Y1-Pad14)") (class "Default")
      (node (ref "U7") (pin "14") (pinfunction "Y1_14") (pintype "output"))
    )
    (net (code "184") (name "unconnected-(U7A-Y2-Pad13)") (class "Default")
      (node (ref "U7") (pin "13") (pinfunction "Y2_13") (pintype "output"))
    )
    (net (code "185") (name "unconnected-(U7A-Y3-Pad12)") (class "Default")
      (node (ref "U7") (pin "12") (pinfunction "Y3_12") (pintype "output"))
    )
    (net (code "186") (name "unconnected-(U7A-Y4-Pad11)") (class "Default")
      (node (ref "U7") (pin "11") (pinfunction "Y4_11") (pintype "output"))
    )
    (net (code "187") (name "unconnected-(U7A-Y5-Pad10)") (class "Default")
      (node (ref "U7") (pin "10") (pinfunction "Y5_10") (pintype "output"))
    )
    (net (code "188") (name "unconnected-(U7A-Y6-Pad9)") (class "Default")
      (node (ref "U7") (pin "9") (pinfunction "Y6_9") (pintype "output"))
    )
    (net (code "189") (name "unconnected-(U8A-Y4-Pad11)") (class "Default")
      (node (ref "U8") (pin "11") (pinfunction "Y4_11") (pintype "output"))
    )
    (net (code "190") (name "unconnected-(U8A-Y5-Pad10)") (class "Default")
      (node (ref "U8") (pin "10") (pinfunction "Y5_10") (pintype "output"))
    )
    (net (code "191") (name "unconnected-(U8A-Y6-Pad9)") (class "Default")
      (node (ref "U8") (pin "9") (pinfunction "Y6_9") (pintype "output"))
    )
    (net (code "192") (name "unconnected-(U8A-Y7-Pad7)") (class "Default")
      (node (ref "U8") (pin "7") (pinfunction "Y7_7") (pintype "output"))
    )
  )
)
